# gripper.net
KiCad netlist of a schematic drawn in EAGLE
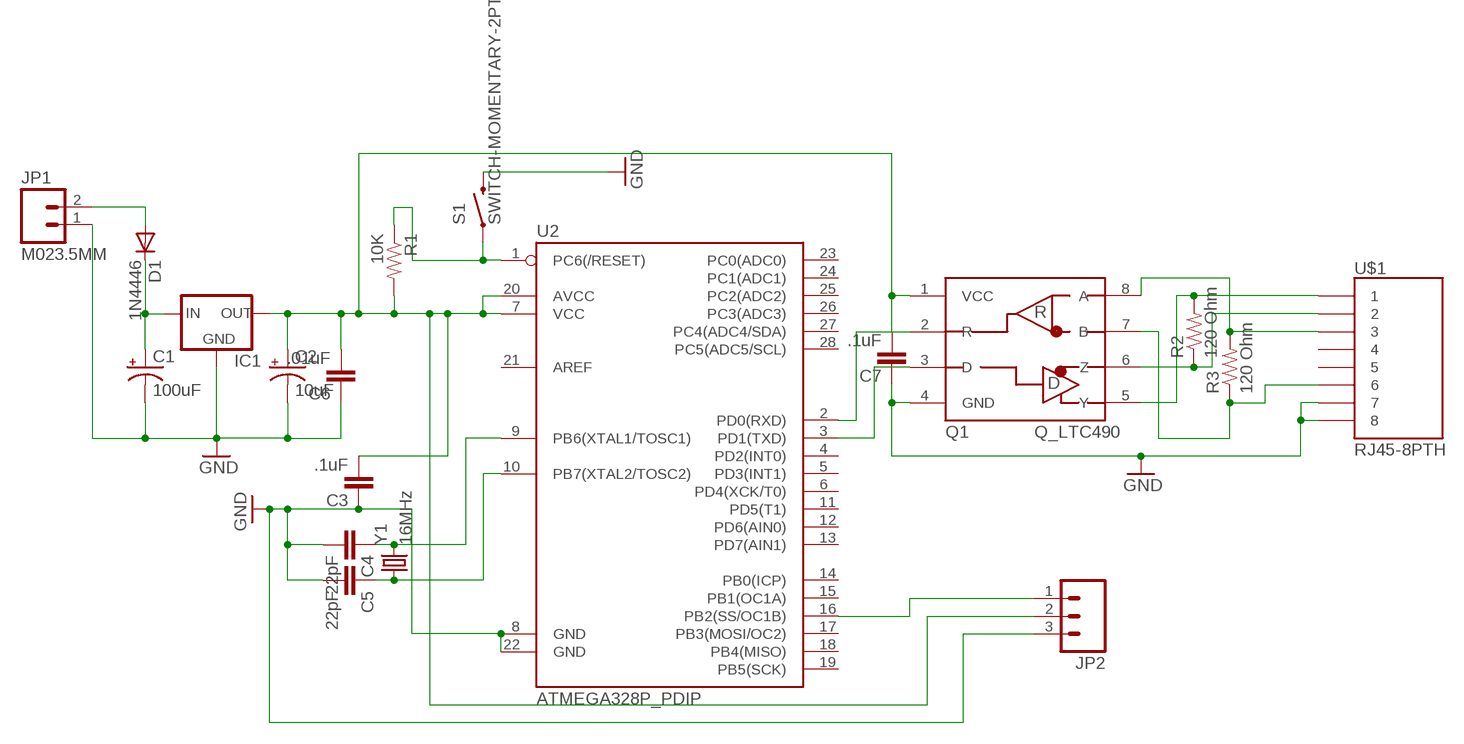
[diagram p0: schematic, sheet 1]

(export (version "E")
  (design (tool "Eeschema 10.0.6"))
  (components
    (comp (ref "C1")
      (value "100uF")
      (footprint "eagle-import:CPOL-RADIAL-100UF-25V")
      (libsource (lib "eagle-import") (part "CAP_POLPTH1"))
    )
    (comp (ref "C2")
      (value "10uF")
      (footprint "eagle-import:CPOL-RADIAL-10UF-25V")
      (libsource (lib "eagle-import") (part "CAP_POLPTH2"))
    )
    (comp (ref "C3")
      (value ".1uF")
      (footprint "eagle-import:CAP-PTH-SMALL-KIT")
      (libsource (lib "eagle-import") (part "CAPKIT"))
    )
    (comp (ref "C4")
      (value "22pF")
      (footprint "eagle-import:CAP-PTH-SMALL-KIT")
      (libsource (lib "eagle-import") (part "CAPKIT"))
    )
    (comp (ref "C5")
      (value "22pF")
      (footprint "eagle-import:CAP-PTH-SMALL-KIT")
      (libsource (lib "eagle-import") (part "CAPKIT"))
    )
    (comp (ref "C6")
      (value ".01uF")
      (footprint "eagle-import:CAP-PTH-SMALL-KIT")
      (libsource (lib "eagle-import") (part "CAPKIT"))
    )
    (comp (ref "C7")
      (value ".1uF")
      (footprint "eagle-import:CAP-PTH-SMALL-KIT")
      (libsource (lib "eagle-import") (part "CAPKIT"))
    )
    (comp (ref "D1")
      (value "1N4446")
      (footprint "eagle-import:DO35-10")
      (libsource (lib "eagle-import") (part "1N4446"))
    )
    (comp (ref "IC1")
      (value "V_REG_78XXTO-92")
      (footprint "eagle-import:TO-92")
      (libsource (lib "eagle-import") (part "V_REG_78XXTO-92"))
    )
    (comp (ref "JP1")
      (value "M023.5MM")
      (footprint "eagle-import:SCREWTERMINAL-3.5MM-2")
      (libsource (lib "eagle-import") (part "M023.5MM"))
    )
    (comp (ref "JP2")
      (value "M03POLAR")
      (footprint "eagle-import:MOLEX-1X3")
      (libsource (lib "eagle-import") (part "M03POLAR"))
    )
    (comp (ref "Q1")
      (value "Q_LTC490")
      (footprint "eagle-import:DIP8")
      (libsource (lib "eagle-import") (part "Q_LTC490"))
    )
    (comp (ref "R1")
      (value "10K")
      (footprint "eagle-import:AXIAL-0.3-KIT")
      (libsource (lib "eagle-import") (part "RESISTORKIT"))
    )
    (comp (ref "R2")
      (value "120 Ohm")
      (footprint "eagle-import:AXIAL-0.3-KIT")
      (libsource (lib "eagle-import") (part "RESISTORKIT"))
    )
    (comp (ref "R3")
      (value "120 Ohm")
      (footprint "eagle-import:AXIAL-0.3-KIT")
      (libsource (lib "eagle-import") (part "RESISTORKIT"))
    )
    (comp (ref "S1")
      (value "SWITCH-MOMENTARY-2PTH")
      (footprint "eagle-import:TACTILE-PTH")
      (libsource (lib "eagle-import") (part "SWITCH-MOMENTARY-2PTH"))
    )
    (comp (ref "U$1")
      (value "RJ45-8PTH")
      (footprint "eagle-import:RJ45-8")
      (libsource (lib "eagle-import") (part "RJ45-8PTH"))
    )
    (comp (ref "U2")
      (value "ATMEGA328P_PDIP")
      (footprint "eagle-import:DIL28-3")
      (libsource (lib "eagle-import") (part "ATMEGA328P_PDIP"))
    )
    (comp (ref "Y1")
      (value "16MHz")
      (footprint "eagle-import:HC49US")
      (libsource (lib "eagle-import") (part "CRYSTALHC49US"))
    )
  )
  (nets
    (net (code "1") (name "GND") (class "Default")
      (node (ref "C1") (pin "2") (pinfunction "-_2") (pintype "passive"))
      (node (ref "C2") (pin "2") (pinfunction "-_2") (pintype "passive"))
      (node (ref "C3") (pin "1") (pinfunction "1_1") (pintype "passive"))
      (node (ref "C4") (pin "2") (pinfunction "2_2") (pintype "passive"))
      (node (ref "C5") (pin "2") (pinfunction "2_2") (pintype "passive"))
      (node (ref "C6") (pin "1") (pinfunction "1_1") (pintype "passive"))
      (node (ref "C7") (pin "1") (pinfunction "1_1") (pintype "passive"))
      (node (ref "IC1") (pin "1") (pinfunction "GND_1") (pintype "input"))
      (node (ref "JP1") (pin "1") (pinfunction "1_1") (pintype "passive"))
      (node (ref "JP2") (pin "3") (pinfunction "3_3") (pintype "passive"))
      (node (ref "Q1") (pin "4") (pinfunction "GND_4") (pintype "bidirectional"))
      (node (ref "S1") (pin "3") (pinfunction "2_3") (pintype "passive"))
      (node (ref "U$1") (pin "7") (pinfunction "7_7") (pintype "bidirectional"))
      (node (ref "U$1") (pin "8") (pinfunction "8_8") (pintype "bidirectional"))
      (node (ref "U2") (pin "22") (pinfunction "GND_22") (pintype "bidirectional"))
      (node (ref "U2") (pin "8") (pinfunction "GND_8") (pintype "bidirectional"))
    )
    (net (code "2") (name "Net-(C1-+)") (class "Default")
      (node (ref "C1") (pin "1") (pinfunction "+_1") (pintype "passive"))
      (node (ref "D1") (pin "C") (pinfunction "C_C") (pintype "passive"))
      (node (ref "IC1") (pin "2") (pinfunction "IN_2") (pintype "input"))
    )
    (net (code "3") (name "Net-(C2-+)") (class "Default")
      (node (ref "C2") (pin "1") (pinfunction "+_1") (pintype "passive"))
      (node (ref "C3") (pin "2") (pinfunction "2_2") (pintype "passive"))
      (node (ref "C6") (pin "2") (pinfunction "2_2") (pintype "passive"))
      (node (ref "C7") (pin "2") (pinfunction "2_2") (pintype "passive"))
      (node (ref "IC1") (pin "3") (pinfunction "OUT_3") (pintype "output"))
      (node (ref "JP2") (pin "2") (pinfunction "2_2") (pintype "passive"))
      (node (ref "Q1") (pin "1") (pinfunction "VCC_1") (pintype "bidirectional"))
      (node (ref "R1") (pin "P$2") (pinfunction "2_P$2") (pintype "passive"))
      (node (ref "U2") (pin "20") (pinfunction "AVCC_20") (pintype "bidirectional"))
      (node (ref "U2") (pin "7") (pinfunction "VCC_7") (pintype "bidirectional"))
    )
    (net (code "4") (name "Net-(D1-PadA)") (class "Default")
      (node (ref "D1") (pin "A") (pinfunction "A_A") (pintype "passive"))
      (node (ref "JP1") (pin "2") (pinfunction "2_2") (pintype "passive"))
    )
    (net (code "5") (name "Net-(Q1-A)") (class "Default")
      (node (ref "Q1") (pin "8") (pinfunction "A_8") (pintype "bidirectional"))
      (node (ref "R3") (pin "P$2") (pinfunction "2_P$2") (pintype "passive"))
      (node (ref "U$1") (pin "3") (pinfunction "3_3") (pintype "bidirectional"))
    )
    (net (code "6") (name "Net-(Q1-B)") (class "Default")
      (node (ref "Q1") (pin "7") (pinfunction "B_7") (pintype "bidirectional"))
      (node (ref "R3") (pin "P$1") (pinfunction "1_P$1") (pintype "passive"))
      (node (ref "U$1") (pin "6") (pinfunction "6_6") (pintype "bidirectional"))
    )
    (net (code "7") (name "Net-(Q1-D)") (class "Default")
      (node (ref "Q1") (pin "3") (pinfunction "D_3") (pintype "bidirectional"))
      (node (ref "U2") (pin "3") (pinfunction "PD1(TXD)_3") (pintype "bidirectional"))
    )
    (net (code "8") (name "Net-(Q1-R)") (class "Default")
      (node (ref "Q1") (pin "2") (pinfunction "R_2") (pintype "bidirectional"))
      (node (ref "U2") (pin "2") (pinfunction "PD0(RXD)_2") (pintype "bidirectional"))
    )
    (net (code "9") (name "Net-(Q1-Y)") (class "Default")
      (node (ref "Q1") (pin "5") (pinfunction "Y_5") (pintype "bidirectional"))
      (node (ref "R2") (pin "P$2") (pinfunction "2_P$2") (pintype "passive"))
      (node (ref "U$1") (pin "1") (pinfunction "1_1") (pintype "bidirectional"))
    )
    (net (code "10") (name "Net-(Q1-Z)") (class "Default")
      (node (ref "Q1") (pin "6") (pinfunction "Z_6") (pintype "bidirectional"))
      (node (ref "R2") (pin "P$1") (pinfunction "1_P$1") (pintype "passive"))
      (node (ref "U$1") (pin "2") (pinfunction "2_2") (pintype "bidirectional"))
    )
    (net (code "11") (name "Net-(R1-1)") (class "Default")
      (node (ref "R1") (pin "P$1") (pinfunction "1_P$1") (pintype "passive"))
      (node (ref "S1") (pin "1") (pinfunction "1_1") (pintype "passive"))
      (node (ref "U2") (pin "1") (pinfunction "PC6(/RESET)_1") (pintype "bidirectional"))
    )
    (net (code "12") (name "Net-(U2-PB2(SS{slash}OC1B))") (class "Default")
      (node (ref "JP2") (pin "1") (pinfunction "1_1") (pintype "passive"))
      (node (ref "U2") (pin "16") (pinfunction "PB2(SS/OC1B)_16") (pintype "bidirectional"))
    )
    (net (code "13") (name "Net-(U2-PB6(XTAL1{slash}TOSC1))") (class "Default")
      (node (ref "C4") (pin "1") (pinfunction "1_1") (pintype "passive"))
      (node (ref "U2") (pin "9") (pinfunction "PB6(XTAL1/TOSC1)_9") (pintype "bidirectional"))
      (node (ref "Y1") (pin "2") (pinfunction "2_2") (pintype "passive"))
    )
    (net (code "14") (name "Net-(U2-PB7(XTAL2{slash}TOSC2))") (class "Default")
      (node (ref "C5") (pin "1") (pinfunction "1_1") (pintype "passive"))
      (node (ref "U2") (pin "10") (pinfunction "PB7(XTAL2/TOSC2)_10") (pintype "bidirectional"))
      (node (ref "Y1") (pin "1") (pinfunction "1_1") (pintype "passive"))
    )
    (net (code "15") (name "unconnected-(U$1-Pad4)") (class "Default")
      (node (ref "U$1") (pin "4") (pinfunction "4_4") (pintype "bidirectional"))
    )
    (net (code "16") (name "unconnected-(U$1-Pad5)") (class "Default")
      (node (ref "U$1") (pin "5") (pinfunction "5_5") (pintype "bidirectional"))
    )
    (net (code "17") (name "unconnected-(U2-AREF-Pad21)") (class "Default")
      (node (ref "U2") (pin "21") (pinfunction "AREF_21") (pintype "bidirectional"))
    )
    (net (code "18") (name "unconnected-(U2-PB0(ICP)-Pad14)") (class "Default")
      (node (ref "U2") (pin "14") (pinfunction "PB0(ICP)_14") (pintype "bidirectional"))
    )
    (net (code "19") (name "unconnected-(U2-PB1(OC1A)-Pad15)") (class "Default")
      (node (ref "U2") (pin "15") (pinfunction "PB1(OC1A)_15") (pintype "bidirectional"))
    )
    (net (code "20") (name "unconnected-(U2-PB3(MOSI{slash}OC2)-Pad17)") (class "Default")
      (node (ref "U2") (pin "17") (pinfunction "PB3(MOSI/OC2)_17") (pintype "bidirectional"))
    )
    (net (code "21") (name "unconnected-(U2-PB4(MISO)-Pad18)") (class "Default")
      (node (ref "U2") (pin "18") (pinfunction "PB4(MISO)_18") (pintype "bidirectional"))
    )
    (net (code "22") (name "unconnected-(U2-PB5(SCK)-Pad19)") (class "Default")
      (node (ref "U2") (pin "19") (pinfunction "PB5(SCK)_19") (pintype "bidirectional"))
    )
    (net (code "23") (name "unconnected-(U2-PC0(ADC0)-Pad23)") (class "Default")
      (node (ref "U2") (pin "23") (pinfunction "PC0(ADC0)_23") (pintype "bidirectional"))
    )
    (net (code "24") (name "unconnected-(U2-PC1(ADC1)-Pad24)") (class "Default")
      (node (ref "U2") (pin "24") (pinfunction "PC1(ADC1)_24") (pintype "bidirectional"))
    )
    (net (code "25") (name "unconnected-(U2-PC2(ADC2)-Pad25)") (class "Default")
      (node (ref "U2") (pin "25") (pinfunction "PC2(ADC2)_25") (pintype "bidirectional"))
    )
    (net (code "26") (name "unconnected-(U2-PC3(ADC3)-Pad26)") (class "Default")
      (node (ref "U2") (pin "26") (pinfunction "PC3(ADC3)_26") (pintype "bidirectional"))
    )
    (net (code "27") (name "unconnected-(U2-PC4(ADC4{slash}SDA)-Pad27)") (class "Default")
      (node (ref "U2") (pin "27") (pinfunction "PC4(ADC4/SDA)_27") (pintype "bidirectional"))
    )
    (net (code "28") (name "unconnected-(U2-PC5(ADC5{slash}SCL)-Pad28)") (class "Default")
      (node (ref "U2") (pin "28") (pinfunction "PC5(ADC5/SCL)_28") (pintype "bidirectional"))
    )
    (net (code "29") (name "unconnected-(U2-PD2(INT0)-Pad4)") (class "Default")
      (node (ref "U2") (pin "4") (pinfunction "PD2(INT0)_4") (pintype "bidirectional"))
    )
    (net (code "30") (name "unconnected-(U2-PD3(INT1)-Pad5)") (class "Default")
      (node (ref "U2") (pin "5") (pinfunction "PD3(INT1)_5") (pintype "bidirectional"))
    )
    (net (code "31") (name "unconnected-(U2-PD4(XCK{slash}T0)-Pad6)") (class "Default")
      (node (ref "U2") (pin "6") (pinfunction "PD4(XCK/T0)_6") (pintype "bidirectional"))
    )
    (net (code "32") (name "unconnected-(U2-PD5(T1)-Pad11)") (class "Default")
      (node (ref "U2") (pin "11") (pinfunction "PD5(T1)_11") (pintype "bidirectional"))
    )
    (net (code "33") (name "unconnected-(U2-PD6(AIN0)-Pad12)") (class "Default")
      (node (ref "U2") (pin "12") (pinfunction "PD6(AIN0)_12") (pintype "bidirectional"))
    )
    (net (code "34") (name "unconnected-(U2-PD7(AIN1)-Pad13)") (class "Default")
      (node (ref "U2") (pin "13") (pinfunction "PD7(AIN1)_13") (pintype "bidirectional"))
    )
  )
)
